# Sheet2.net
KiCad netlist of a schematic drawn in Altium Designer
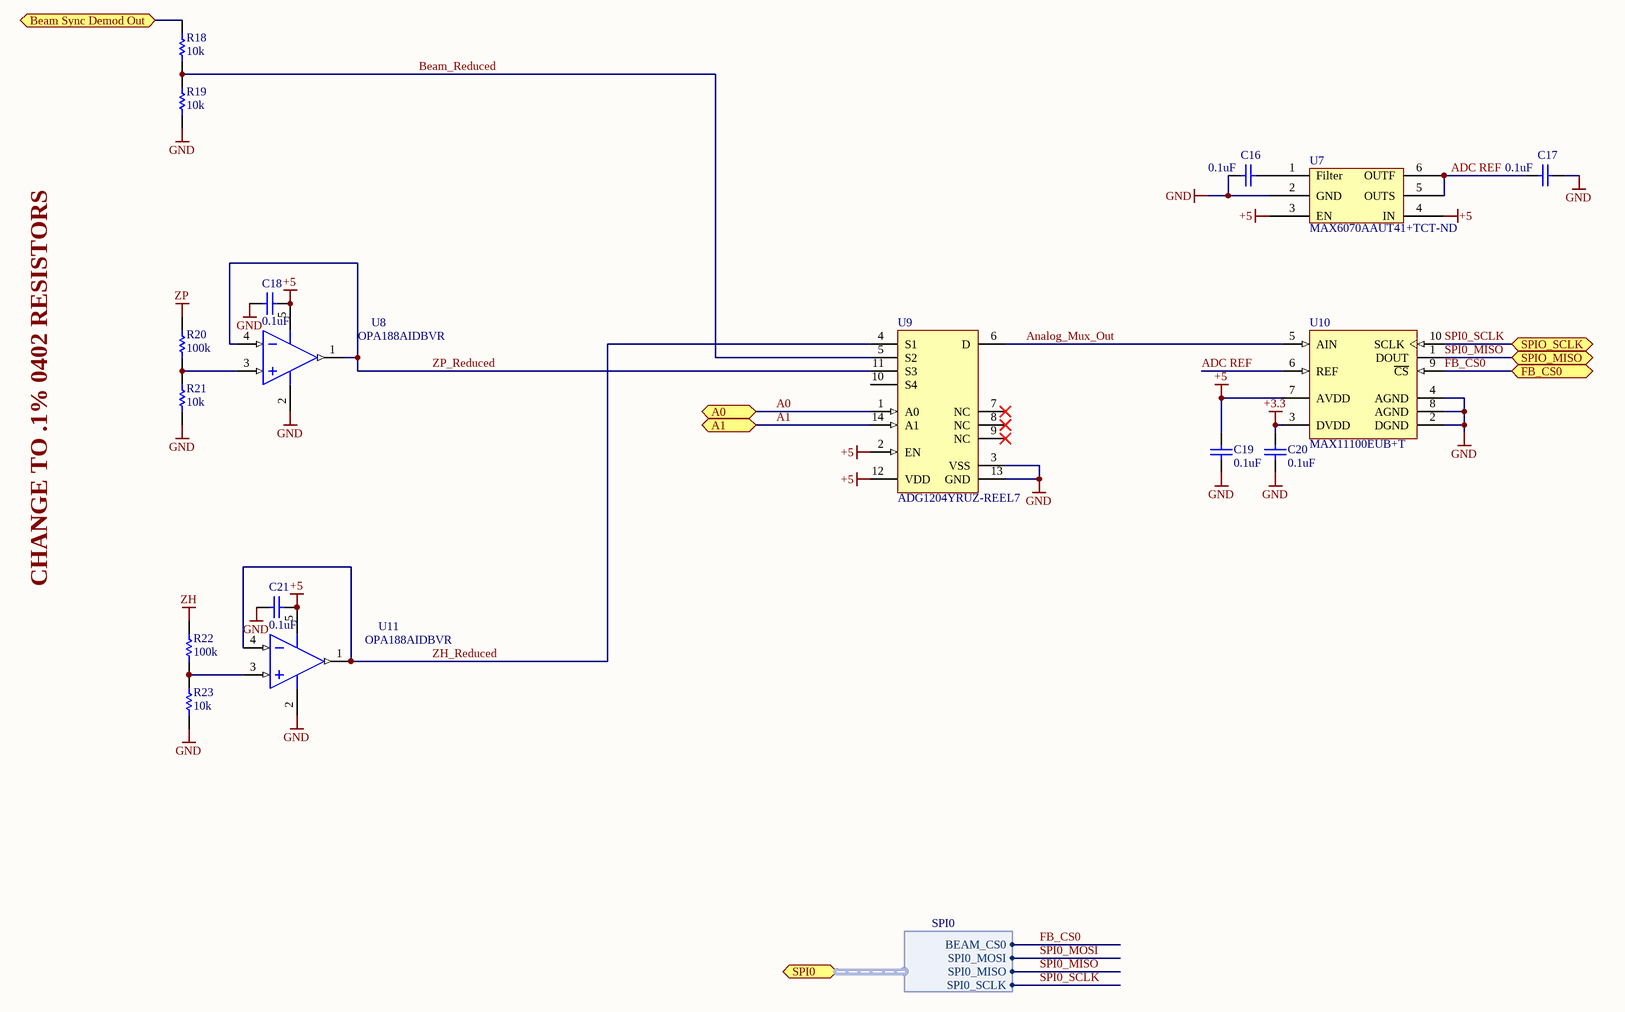
[diagram p0: Sheet2.SchDoc]

(export (version "E")
  (design (tool "Eeschema 10.0.6"))
  (components
    (comp (ref "C16")
      (value "0.1uF")
      (footprint "CAPC0402(1005)60_L")
      (description "CAP CER 0.1UF 10V X7R 0402")
      (fields
        (field (name "MANUFACTURER") "Murata Electronics North America")
        (field (name "MANUFACTURER PART NUMBER") "GRM155R71A104KA01D")
      )
      (libsource (lib "Altium Content Vault") (part "CMP-1034-00252-1"))
    )
    (comp (ref "C17")
      (value "0.1uF")
      (footprint "CAPC0402(1005)60_L")
      (description "CAP CER 0.1UF 10V X7R 0402")
      (fields
        (field (name "MANUFACTURER") "Murata Electronics North America")
        (field (name "MANUFACTURER PART NUMBER") "GRM155R71A104KA01D")
      )
      (libsource (lib "Altium Content Vault") (part "CMP-1034-00252-1"))
    )
    (comp (ref "C18")
      (value "0.1uF")
      (footprint "CAPC0402(1005)60_L")
      (description "CAP CER 0.1UF 10V X7R 0402")
      (fields
        (field (name "MANUFACTURER") "Murata Electronics North America")
        (field (name "MANUFACTURER PART NUMBER") "GRM155R71A104KA01D")
      )
      (libsource (lib "Altium Content Vault") (part "CMP-1034-00252-1"))
    )
    (comp (ref "C19")
      (value "0.1uF")
      (footprint "CAPC0402(1005)60_L")
      (description "CAP CER 0.1UF 10V X7R 0402")
      (fields
        (field (name "MANUFACTURER") "Murata Electronics North America")
        (field (name "MANUFACTURER PART NUMBER") "GRM155R71A104KA01D")
      )
      (libsource (lib "Altium Content Vault") (part "CMP-1034-00252-1"))
    )
    (comp (ref "C20")
      (value "0.1uF")
      (footprint "CAPC0402(1005)60_L")
      (description "CAP CER 0.1UF 10V X7R 0402")
      (fields
        (field (name "MANUFACTURER") "Murata Electronics North America")
        (field (name "MANUFACTURER PART NUMBER") "GRM155R71A104KA01D")
      )
      (libsource (lib "Altium Content Vault") (part "CMP-1034-00252-1"))
    )
    (comp (ref "C21")
      (value "0.1uF")
      (footprint "CAPC0402(1005)60_L")
      (description "CAP CER 0.1UF 10V X7R 0402")
      (fields
        (field (name "MANUFACTURER") "Murata Electronics North America")
        (field (name "MANUFACTURER PART NUMBER") "GRM155R71A104KA01D")
      )
      (libsource (lib "Altium Content Vault") (part "CMP-1034-00252-1"))
    )
    (comp (ref "R18")
      (value "10k")
      (footprint "RESC0402(1005)_M")
      (description "RES SMD 10K OHM 1% 1/8W 0402")
      (fields
        (field (name "MANUFACTURER") "Vishay Dale")
        (field (name "MANUFACTURER PART NUMBER") "CRCW0402100KFKEDHP")
      )
      (libsource (lib "Altium Content Vault") (part "CMP-1011-00651-1"))
    )
    (comp (ref "R19")
      (value "10k")
      (footprint "RESC0402(1005)_M")
      (description "RES SMD 10K OHM 1% 1/8W 0402")
      (fields
        (field (name "MANUFACTURER") "Vishay Dale")
        (field (name "MANUFACTURER PART NUMBER") "CRCW0402100KFKEDHP")
      )
      (libsource (lib "Altium Content Vault") (part "CMP-1011-00651-1"))
    )
    (comp (ref "R20")
      (value "100k")
      (footprint "RESC0402(1005)_M")
      (description "RES SMD 100K OHM 1% 1/8W 0402")
      (fields
        (field (name "MANUFACTURER") "Vishay Dale")
        (field (name "MANUFACTURER PART NUMBER") "CRCW0402100KFKEDHP")
      )
      (libsource (lib "Altium Content Vault") (part "CMP-1011-00651-1"))
    )
    (comp (ref "R21")
      (value "10k")
      (footprint "RESC0402(1005)_M")
      (description "RES SMD 10K OHM 1% 1/8W 0402")
      (fields
        (field (name "MANUFACTURER") "Vishay Dale")
        (field (name "MANUFACTURER PART NUMBER") "CRCW0402100KFKEDHP")
      )
      (libsource (lib "Altium Content Vault") (part "CMP-1011-00651-1"))
    )
    (comp (ref "R22")
      (value "100k")
      (footprint "RESC0402(1005)_M")
      (description "RES SMD 100K OHM 1% 1/8W 0402")
      (fields
        (field (name "MANUFACTURER") "Vishay Dale")
        (field (name "MANUFACTURER PART NUMBER") "CRCW0402100KFKEDHP")
      )
      (libsource (lib "Altium Content Vault") (part "CMP-1011-00651-1"))
    )
    (comp (ref "R23")
      (value "10k")
      (footprint "RESC0402(1005)_M")
      (description "RES SMD 10K OHM 1% 1/8W 0402")
      (fields
        (field (name "MANUFACTURER") "Vishay Dale")
        (field (name "MANUFACTURER PART NUMBER") "CRCW0402100KFKEDHP")
      )
      (libsource (lib "Altium Content Vault") (part "CMP-1011-00651-1"))
    )
    (comp (ref "U7")
      (value "MAX6070AAUT41+T")
      (footprint "SOT95P280X445-6N")
      (description "IC VREF SERIES 4.096V SOT23")
      (fields
        (field (name "SUPPLIER PART NUMBER 1") "MAX6070AAUT41+TCT-ND")
        (field (name "MANUFACTURER") "Maxim Integrated")
        (field (name "TOLERANCE") "±0.04%")
      )
      (libsource (lib "ZLS_Schematic_lib") (part "MAX6070AAUT41+T"))
    )
    (comp (ref "U8")
      (value "OPA188AIDBVR")
      (footprint "DBV0005A_M")
      (fields (field (name "MANUFACTURER") "Texas Instruments"))
      (libsource (lib "Altium Content Vault") (part "CMP-0809-00005-2"))
    )
    (comp (ref "U9")
      (value "ADG1204YRUZ-REEL7")
      (footprint "ADI-RU-14_L")
      (fields (field (name "MANUFACTURER") "Analog Devices"))
      (libsource (lib "Altium Content Vault") (part "ADI-ADG1204-RU-14"))
    )
    (comp (ref "U10")
      (value "MAX11100EUB+T")
      (footprint "U10+2_L")
      (description "16-Bit, +5V, 200ksps ADC with 10uA Shutdown, 10-Pin uMAX, -40°C to +85°C, Pb-Free, Tape and Reel")
      (libsource (lib "Altium Content Vault") (part "CON-ADC-MAX11100-IL10"))
    )
    (comp (ref "U11")
      (value "OPA188AIDBVR")
      (footprint "DBV0005A_M")
      (fields (field (name "MANUFACTURER") "Texas Instruments"))
      (libsource (lib "Altium Content Vault") (part "CMP-0809-00005-2"))
    )
  )
  (nets
    (net (code "2") (name "+3.3") (class "Default")
      (node (ref "C20") (pin "1") (pinfunction "1_1") (pintype "passive"))
      (node (ref "U10") (pin "3") (pinfunction "DVDD_3") (pintype "power_in"))
    )
    (net (code "3") (name "+5") (class "Default")
      (node (ref "C18") (pin "2") (pinfunction "2_2") (pintype "passive"))
      (node (ref "C19") (pin "1") (pinfunction "1_1") (pintype "passive"))
      (node (ref "C21") (pin "2") (pinfunction "2_2") (pintype "passive"))
      (node (ref "U10") (pin "7") (pinfunction "AVDD_7") (pintype "power_in"))
      (node (ref "U11") (pin "5") (pinfunction "V+_5") (pintype "power_in"))
      (node (ref "U7") (pin "3") (pinfunction "EN_3") (pintype "passive"))
      (node (ref "U7") (pin "4") (pinfunction "IN_4") (pintype "passive"))
      (node (ref "U8") (pin "5") (pinfunction "V+_5") (pintype "power_in"))
      (node (ref "U9") (pin "12") (pinfunction "VDD_12") (pintype "power_in"))
      (node (ref "U9") (pin "2") (pinfunction "EN_2") (pintype "input"))
    )
    (net (code "4") (name "/A0") (class "Default")
      (node (ref "U9") (pin "1") (pinfunction "A0_1") (pintype "input"))
    )
    (net (code "5") (name "/A1") (class "Default")
      (node (ref "U9") (pin "14") (pinfunction "A1_14") (pintype "input"))
    )
    (net (code "6") (name "/ADC REF") (class "Default")
      (node (ref "C17") (pin "2") (pinfunction "2_2") (pintype "passive"))
      (node (ref "U10") (pin "6") (pinfunction "REF_6") (pintype "input"))
      (node (ref "U7") (pin "5") (pinfunction "OUTS_5") (pintype "passive"))
      (node (ref "U7") (pin "6") (pinfunction "OUTF_6") (pintype "passive"))
    )
    (net (code "7") (name "/Analog_Mux_Out") (class "Default")
      (node (ref "U10") (pin "5") (pinfunction "AIN_5") (pintype "input"))
      (node (ref "U9") (pin "6") (pinfunction "D_6") (pintype "passive"))
    )
    (net (code "8") (name "/Beam Sync Demod Out") (class "Default")
      (node (ref "R18") (pin "2") (pinfunction "2_2") (pintype "passive"))
    )
    (net (code "9") (name "/Beam_Reduced") (class "Default")
      (node (ref "R18") (pin "1") (pinfunction "1_1") (pintype "passive"))
      (node (ref "R19") (pin "2") (pinfunction "2_2") (pintype "passive"))
      (node (ref "U9") (pin "5") (pinfunction "S2_5") (pintype "passive"))
    )
    (net (code "10") (name "/FB_CS0") (class "Default")
      (node (ref "U10") (pin "9") (pinfunction "~{CS}_9") (pintype "input"))
    )
    (net (code "11") (name "/SPI0_MISO") (class "Default")
      (node (ref "U10") (pin "1") (pinfunction "DOUT_1") (pintype "tri_state"))
    )
    (net (code "13") (name "/SPI0_SCLK") (class "Default")
      (node (ref "U10") (pin "10") (pinfunction "SCLK_10") (pintype "input"))
    )
    (net (code "14") (name "/ZH_Reduced") (class "Default")
      (node (ref "U11") (pin "1") (pinfunction "OUT_1") (pintype "output"))
      (node (ref "U11") (pin "4") (pinfunction "IN-_4") (pintype "input"))
      (node (ref "U9") (pin "4") (pinfunction "S1_4") (pintype "passive"))
    )
    (net (code "15") (name "/ZP_Reduced") (class "Default")
      (node (ref "U8") (pin "1") (pinfunction "OUT_1") (pintype "output"))
      (node (ref "U8") (pin "4") (pinfunction "IN-_4") (pintype "input"))
      (node (ref "U9") (pin "11") (pinfunction "S3_11") (pintype "passive"))
    )
    (net (code "17") (name "GND") (class "Default")
      (node (ref "C16") (pin "2") (pinfunction "2_2") (pintype "passive"))
      (node (ref "C17") (pin "1") (pinfunction "1_1") (pintype "passive"))
      (node (ref "C18") (pin "1") (pinfunction "1_1") (pintype "passive"))
      (node (ref "C19") (pin "2") (pinfunction "2_2") (pintype "passive"))
      (node (ref "C20") (pin "2") (pinfunction "2_2") (pintype "passive"))
      (node (ref "C21") (pin "1") (pinfunction "1_1") (pintype "passive"))
      (node (ref "R19") (pin "1") (pinfunction "1_1") (pintype "passive"))
      (node (ref "R21") (pin "1") (pinfunction "1_1") (pintype "passive"))
      (node (ref "R23") (pin "1") (pinfunction "1_1") (pintype "passive"))
      (node (ref "U10") (pin "2") (pinfunction "DGND_2") (pintype "power_in"))
      (node (ref "U10") (pin "4") (pinfunction "AGND_4") (pintype "power_in"))
      (node (ref "U10") (pin "8") (pinfunction "AGND_8") (pintype "power_in"))
      (node (ref "U11") (pin "2") (pinfunction "V-_2") (pintype "power_in"))
      (node (ref "U7") (pin "2") (pinfunction "GND_2") (pintype "passive"))
      (node (ref "U8") (pin "2") (pinfunction "V-_2") (pintype "power_in"))
      (node (ref "U9") (pin "13") (pinfunction "GND_13") (pintype "power_in"))
      (node (ref "U9") (pin "3") (pinfunction "VSS_3") (pintype "power_in"))
    )
    (net (code "18") (name "Net-(U7-Filter)") (class "Default")
      (node (ref "C16") (pin "1") (pinfunction "1_1") (pintype "passive"))
      (node (ref "U7") (pin "1") (pinfunction "Filter_1") (pintype "passive"))
    )
    (net (code "19") (name "Net-(U8-IN+)") (class "Default")
      (node (ref "R20") (pin "1") (pinfunction "1_1") (pintype "passive"))
      (node (ref "R21") (pin "2") (pinfunction "2_2") (pintype "passive"))
      (node (ref "U8") (pin "3") (pinfunction "IN+_3") (pintype "input"))
    )
    (net (code "20") (name "Net-(U11-IN+)") (class "Default")
      (node (ref "R22") (pin "1") (pinfunction "1_1") (pintype "passive"))
      (node (ref "R23") (pin "2") (pinfunction "2_2") (pintype "passive"))
      (node (ref "U11") (pin "3") (pinfunction "IN+_3") (pintype "input"))
    )
    (net (code "21") (name "ZH") (class "Default")
      (node (ref "R22") (pin "2") (pinfunction "2_2") (pintype "passive"))
    )
    (net (code "22") (name "ZP") (class "Default")
      (node (ref "R20") (pin "2") (pinfunction "2_2") (pintype "passive"))
    )
    (net (code "23") (name "unconnected-(U9-NC-Pad7)") (class "Default")
      (node (ref "U9") (pin "7") (pinfunction "NC_7") (pintype "passive+no_connect"))
    )
    (net (code "24") (name "unconnected-(U9-NC-Pad8)") (class "Default")
      (node (ref "U9") (pin "8") (pinfunction "NC_8") (pintype "passive+no_connect"))
    )
    (net (code "25") (name "unconnected-(U9-NC-Pad9)") (class "Default")
      (node (ref "U9") (pin "9") (pinfunction "NC_9") (pintype "passive+no_connect"))
    )
    (net (code "26") (name "unconnected-(U9-S4-Pad10)") (class "Default")
      (node (ref "U9") (pin "10") (pinfunction "S4_10") (pintype "passive"))
    )
  )
)
